# Hamamatsu_acond_2.net
KiCad netlist of a schematic drawn in Altium Designer
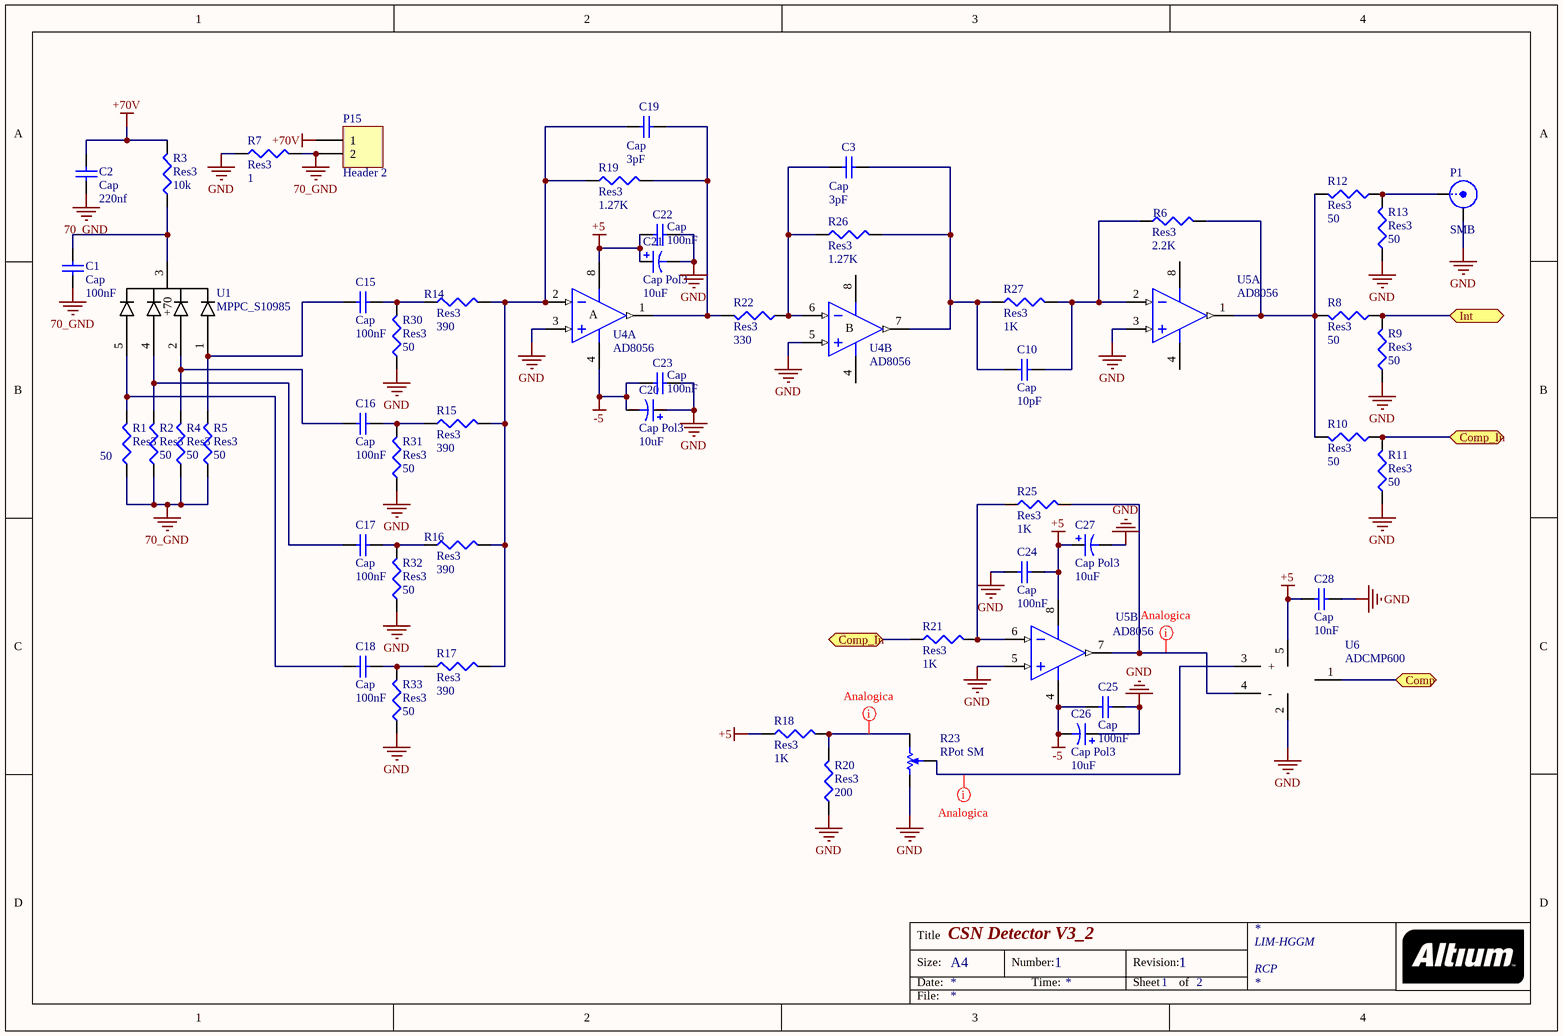
[diagram p0: Hamamatsu_acond_2.SchDoc]

(export (version "E")
  (design (tool "Eeschema 10.0.6"))
  (components
    (comp (ref "C1")
      (value "Cap")
      (footprint "C0805")
      (description "Capacitor")
      (fields (field (name "ALTIUM_VALUE") "100nF") (field (name "PUBLISHER") "Altium Limited"))
      (libsource (lib "Miscellaneous Devices") (part "Cap"))
    )
    (comp (ref "C2")
      (value "Cap")
      (footprint "C0805")
      (description "Capacitor")
      (fields (field (name "ALTIUM_VALUE") "220nf") (field (name "PUBLISHER") "Altium Limited"))
      (libsource (lib "Miscellaneous Devices") (part "Cap"))
    )
    (comp (ref "C3")
      (value "Cap")
      (footprint "C0805")
      (description "Capacitor")
      (fields (field (name "ALTIUM_VALUE") "3pF") (field (name "PUBLISHER") "Altium Limited"))
      (libsource (lib "Miscellaneous Devices") (part "Cap"))
    )
    (comp (ref "C10")
      (value "Cap")
      (footprint "C0805")
      (description "Capacitor")
      (fields (field (name "ALTIUM_VALUE") "10pF") (field (name "PUBLISHER") "Altium Limited"))
      (libsource (lib "Miscellaneous Devices") (part "Cap"))
    )
    (comp (ref "C15")
      (value "Cap")
      (footprint "C0805")
      (description "Capacitor")
      (fields (field (name "ALTIUM_VALUE") "100nF") (field (name "PUBLISHER") "Altium Limited"))
      (libsource (lib "Miscellaneous Devices") (part "Cap"))
    )
    (comp (ref "C16")
      (value "Cap")
      (footprint "C0805")
      (description "Capacitor")
      (fields (field (name "ALTIUM_VALUE") "100nF") (field (name "PUBLISHER") "Altium Limited"))
      (libsource (lib "Miscellaneous Devices") (part "Cap"))
    )
    (comp (ref "C17")
      (value "Cap")
      (footprint "C0805")
      (description "Capacitor")
      (fields (field (name "ALTIUM_VALUE") "100nF") (field (name "PUBLISHER") "Altium Limited"))
      (libsource (lib "Miscellaneous Devices") (part "Cap"))
    )
    (comp (ref "C18")
      (value "Cap")
      (footprint "C0805")
      (description "Capacitor")
      (fields (field (name "ALTIUM_VALUE") "100nF") (field (name "PUBLISHER") "Altium Limited"))
      (libsource (lib "Miscellaneous Devices") (part "Cap"))
    )
    (comp (ref "C19")
      (value "Cap")
      (footprint "C0805")
      (description "Capacitor")
      (fields (field (name "ALTIUM_VALUE") "3pF") (field (name "PUBLISHER") "Altium Limited"))
      (libsource (lib "Miscellaneous Devices") (part "Cap"))
    )
    (comp (ref "C20")
      (value "Cap Pol3")
      (footprint "6-0805_N")
      (description "Polarized Capacitor (Surface Mount)")
      (fields (field (name "ALTIUM_VALUE") "10uF") (field (name "PUBLISHER") "Altium Limited"))
      (libsource (lib "Miscellaneous Devices") (part "Cap Pol3"))
    )
    (comp (ref "C21")
      (value "Cap Pol3")
      (footprint "6-0805_N")
      (description "Polarized Capacitor (Surface Mount)")
      (fields (field (name "ALTIUM_VALUE") "10uF") (field (name "PUBLISHER") "Altium Limited"))
      (libsource (lib "Miscellaneous Devices") (part "Cap Pol3"))
    )
    (comp (ref "C22")
      (value "Cap")
      (footprint "6-0805_N")
      (description "Capacitor")
      (fields (field (name "ALTIUM_VALUE") "100nF") (field (name "PUBLISHER") "Altium Limited"))
      (libsource (lib "Miscellaneous Devices") (part "Cap"))
    )
    (comp (ref "C23")
      (value "Cap")
      (footprint "6-0805_N")
      (description "Capacitor")
      (fields (field (name "ALTIUM_VALUE") "100nF") (field (name "PUBLISHER") "Altium Limited"))
      (libsource (lib "Miscellaneous Devices") (part "Cap"))
    )
    (comp (ref "C24")
      (value "Cap")
      (footprint "6-0805_N")
      (description "Capacitor")
      (fields (field (name "ALTIUM_VALUE") "100nF") (field (name "PUBLISHER") "Altium Limited"))
      (libsource (lib "Miscellaneous Devices") (part "Cap"))
    )
    (comp (ref "C25")
      (value "Cap")
      (footprint "6-0805_N")
      (description "Capacitor")
      (fields (field (name "ALTIUM_VALUE") "100nF") (field (name "PUBLISHER") "Altium Limited"))
      (libsource (lib "Miscellaneous Devices") (part "Cap"))
    )
    (comp (ref "C26")
      (value "Cap Pol3")
      (footprint "6-0805_N")
      (description "Polarized Capacitor (Surface Mount)")
      (fields (field (name "ALTIUM_VALUE") "10uF") (field (name "PUBLISHER") "Altium Limited"))
      (libsource (lib "Miscellaneous Devices") (part "Cap Pol3"))
    )
    (comp (ref "C27")
      (value "Cap Pol3")
      (footprint "6-0805_N")
      (description "Polarized Capacitor (Surface Mount)")
      (fields (field (name "ALTIUM_VALUE") "10uF") (field (name "PUBLISHER") "Altium Limited"))
      (libsource (lib "Miscellaneous Devices") (part "Cap Pol3"))
    )
    (comp (ref "C28")
      (value "Cap")
      (footprint "6-0805_N")
      (description "Capacitor")
      (fields (field (name "ALTIUM_VALUE") "10nF") (field (name "PUBLISHER") "Altium Limited"))
      (libsource (lib "Miscellaneous Devices") (part "Cap"))
    )
    (comp (ref "P1")
      (value "SMB")
      (footprint "SMB_V-RJ45")
      (description "SMB Straight Connector")
      (fields (field (name "PUBLISHER") "Altium Limited"))
      (libsource (lib "Miscellaneous Connectors") (part "SMB"))
    )
    (comp (ref "P15")
      (value "Header 2")
      (footprint "HDR1X2")
      (description "Header, 2-Pin")
      (fields (field (name "PUBLISHER") "Altium Limited"))
      (libsource (lib "Miscellaneous Connectors") (part "Header 2"))
    )
    (comp (ref "R1")
      (value "Res3")
      (footprint "6-0805_N")
      (description "Resistor")
      (fields (field (name "ALTIUM_VALUE") "50") (field (name "PUBLISHER") "Altium Limited"))
      (libsource (lib "Miscellaneous Devices") (part "Res3"))
    )
    (comp (ref "R2")
      (value "Res3")
      (footprint "6-0805_N")
      (description "Resistor")
      (fields (field (name "ALTIUM_VALUE") "50") (field (name "PUBLISHER") "Altium Limited"))
      (libsource (lib "Miscellaneous Devices") (part "Res3"))
    )
    (comp (ref "R3")
      (value "Res3")
      (footprint "6-0805_N")
      (description "Resistor")
      (fields (field (name "ALTIUM_VALUE") "10k") (field (name "PUBLISHER") "Altium Limited"))
      (libsource (lib "Miscellaneous Devices") (part "Res3"))
    )
    (comp (ref "R4")
      (value "Res3")
      (footprint "6-0805_N")
      (description "Resistor")
      (fields (field (name "ALTIUM_VALUE") "50") (field (name "PUBLISHER") "Altium Limited"))
      (libsource (lib "Miscellaneous Devices") (part "Res3"))
    )
    (comp (ref "R5")
      (value "Res3")
      (footprint "6-0805_N")
      (description "Resistor")
      (fields (field (name "ALTIUM_VALUE") "50") (field (name "PUBLISHER") "Altium Limited"))
      (libsource (lib "Miscellaneous Devices") (part "Res3"))
    )
    (comp (ref "R6")
      (value "Res3")
      (footprint "6-0805_N")
      (description "Resistor")
      (fields (field (name "ALTIUM_VALUE") "2.2K") (field (name "PUBLISHER") "Altium Limited"))
      (libsource (lib "Miscellaneous Devices") (part "Res3"))
    )
    (comp (ref "R7")
      (value "Res3")
      (footprint "6-0805_N")
      (description "Resistor")
      (fields (field (name "ALTIUM_VALUE") "1") (field (name "PUBLISHER") "Altium Limited"))
      (libsource (lib "Miscellaneous Devices") (part "Res3"))
    )
    (comp (ref "R8")
      (value "Res3")
      (footprint "6-0805_N")
      (description "Resistor")
      (fields (field (name "ALTIUM_VALUE") "50") (field (name "PUBLISHER") "Altium Limited"))
      (libsource (lib "Miscellaneous Devices") (part "Res3"))
    )
    (comp (ref "R9")
      (value "Res3")
      (footprint "6-0805_N")
      (description "Resistor")
      (fields (field (name "ALTIUM_VALUE") "50") (field (name "PUBLISHER") "Altium Limited"))
      (libsource (lib "Miscellaneous Devices") (part "Res3"))
    )
    (comp (ref "R10")
      (value "Res3")
      (footprint "6-0805_N")
      (description "Resistor")
      (fields (field (name "ALTIUM_VALUE") "50") (field (name "PUBLISHER") "Altium Limited"))
      (libsource (lib "Miscellaneous Devices") (part "Res3"))
    )
    (comp (ref "R11")
      (value "Res3")
      (footprint "6-0805_N")
      (description "Resistor")
      (fields (field (name "ALTIUM_VALUE") "50") (field (name "PUBLISHER") "Altium Limited"))
      (libsource (lib "Miscellaneous Devices") (part "Res3"))
    )
    (comp (ref "R12")
      (value "Res3")
      (footprint "6-0805_N")
      (description "Resistor")
      (fields (field (name "ALTIUM_VALUE") "50") (field (name "PUBLISHER") "Altium Limited"))
      (libsource (lib "Miscellaneous Devices") (part "Res3"))
    )
    (comp (ref "R13")
      (value "Res3")
      (footprint "6-0805_N")
      (description "Resistor")
      (fields (field (name "ALTIUM_VALUE") "50") (field (name "PUBLISHER") "Altium Limited"))
      (libsource (lib "Miscellaneous Devices") (part "Res3"))
    )
    (comp (ref "R14")
      (value "Res3")
      (footprint "6-0805_N")
      (description "Resistor")
      (fields (field (name "ALTIUM_VALUE") "390") (field (name "PUBLISHER") "Altium Limited"))
      (libsource (lib "Miscellaneous Devices") (part "Res3"))
    )
    (comp (ref "R15")
      (value "Res3")
      (footprint "6-0805_N")
      (description "Resistor")
      (fields (field (name "ALTIUM_VALUE") "390") (field (name "PUBLISHER") "Altium Limited"))
      (libsource (lib "Miscellaneous Devices") (part "Res3"))
    )
    (comp (ref "R16")
      (value "Res3")
      (footprint "6-0805_N")
      (description "Resistor")
      (fields (field (name "ALTIUM_VALUE") "390") (field (name "PUBLISHER") "Altium Limited"))
      (libsource (lib "Miscellaneous Devices") (part "Res3"))
    )
    (comp (ref "R17")
      (value "Res3")
      (footprint "6-0805_N")
      (description "Resistor")
      (fields (field (name "ALTIUM_VALUE") "390") (field (name "PUBLISHER") "Altium Limited"))
      (libsource (lib "Miscellaneous Devices") (part "Res3"))
    )
    (comp (ref "R18")
      (value "Res3")
      (footprint "6-0805_N")
      (description "Resistor")
      (fields (field (name "ALTIUM_VALUE") "1K") (field (name "PUBLISHER") "Altium Limited"))
      (libsource (lib "Miscellaneous Devices") (part "Res3"))
    )
    (comp (ref "R19")
      (value "Res3")
      (footprint "6-0805_N")
      (description "Resistor")
      (fields (field (name "ALTIUM_VALUE") "1.27K") (field (name "PUBLISHER") "Altium Limited"))
      (libsource (lib "Miscellaneous Devices") (part "Res3"))
    )
    (comp (ref "R20")
      (value "Res3")
      (footprint "6-0805_N")
      (description "Resistor")
      (fields (field (name "ALTIUM_VALUE") "200") (field (name "PUBLISHER") "Altium Limited"))
      (libsource (lib "Miscellaneous Devices") (part "Res3"))
    )
    (comp (ref "R21")
      (value "Res3")
      (footprint "6-0805_N")
      (description "Resistor")
      (fields (field (name "ALTIUM_VALUE") "1K") (field (name "PUBLISHER") "Altium Limited"))
      (libsource (lib "Miscellaneous Devices") (part "Res3"))
    )
    (comp (ref "R22")
      (value "Res3")
      (footprint "6-0805_N")
      (description "Resistor")
      (fields (field (name "ALTIUM_VALUE") "330") (field (name "PUBLISHER") "Altium Limited"))
      (libsource (lib "Miscellaneous Devices") (part "Res3"))
    )
    (comp (ref "R23")
      (value "RPot SM")
      (footprint "POT4MM-2")
      (description "Square Trimming Potentiometer")
      (fields (field (name "PUBLISHER") "Altium Limited"))
      (libsource (lib "Miscellaneous Devices") (part "RPot SM"))
    )
    (comp (ref "R25")
      (value "Res3")
      (footprint "6-0805_N")
      (description "Resistor")
      (fields (field (name "ALTIUM_VALUE") "1K") (field (name "PUBLISHER") "Altium Limited"))
      (libsource (lib "Miscellaneous Devices") (part "Res3"))
    )
    (comp (ref "R26")
      (value "Res3")
      (footprint "6-0805_N")
      (description "Resistor")
      (fields (field (name "ALTIUM_VALUE") "1.27K") (field (name "PUBLISHER") "Altium Limited"))
      (libsource (lib "Miscellaneous Devices") (part "Res3"))
    )
    (comp (ref "R27")
      (value "Res3")
      (footprint "6-0805_N")
      (description "Resistor")
      (fields (field (name "ALTIUM_VALUE") "1K") (field (name "PUBLISHER") "Altium Limited"))
      (libsource (lib "Miscellaneous Devices") (part "Res3"))
    )
    (comp (ref "R30")
      (value "Res3")
      (footprint "6-0805_N")
      (description "Resistor")
      (fields (field (name "ALTIUM_VALUE") "50") (field (name "PUBLISHER") "Altium Limited"))
      (libsource (lib "Miscellaneous Devices") (part "Res3"))
    )
    (comp (ref "R31")
      (value "Res3")
      (footprint "6-0805_N")
      (description "Resistor")
      (fields (field (name "ALTIUM_VALUE") "50") (field (name "PUBLISHER") "Altium Limited"))
      (libsource (lib "Miscellaneous Devices") (part "Res3"))
    )
    (comp (ref "R32")
      (value "Res3")
      (footprint "6-0805_N")
      (description "Resistor")
      (fields (field (name "ALTIUM_VALUE") "50") (field (name "PUBLISHER") "Altium Limited"))
      (libsource (lib "Miscellaneous Devices") (part "Res3"))
    )
    (comp (ref "R33")
      (value "Res3")
      (footprint "6-0805_N")
      (description "Resistor")
      (fields (field (name "ALTIUM_VALUE") "50") (field (name "PUBLISHER") "Altium Limited"))
      (libsource (lib "Miscellaneous Devices") (part "Res3"))
    )
    (comp (ref "U1")
      (value "MPPC_S10985")
      (footprint "S10985_HAM")
      (libsource (lib "Int_Lib1") (part "MPPC_S10985"))
    )
    (comp (ref "U4")
      (value "AD8056")
      (footprint "SO-8_M")
      (description "Dual 600MHz, 50mW Current Feedback Amplifier")
      (fields (field (name "PUBLISHER") "Altium Limited"))
      (libsource (lib "AD Operational Amplifier") (part "AD8002AR"))
    )
    (comp (ref "U5")
      (value "AD8056")
      (footprint "S8_N")
      (description "Low Cost Dual Video Amplifier")
      (fields (field (name "PUBLISHER") "Altium Limited"))
      (libsource (lib "LT Video Amplifier") (part "LT1253CS8"))
    )
    (comp (ref "U6") (value "ADCMP600") (footprint "SOT23-5_N") (libsource (lib "Schlib1") (part "ADCMP600")))
  )
  (nets
    (net (code "1") (name "+5") (class "Default")
      (node (ref "C21") (pin "1") (pinfunction "1_1") (pintype "passive"))
      (node (ref "C22") (pin "2") (pinfunction "2_2") (pintype "passive"))
      (node (ref "C24") (pin "2") (pinfunction "2_2") (pintype "passive"))
      (node (ref "C27") (pin "1") (pinfunction "1_1") (pintype "passive"))
      (node (ref "C28") (pin "1") (pinfunction "1_1") (pintype "passive"))
      (node (ref "R18") (pin "1") (pinfunction "1_1") (pintype "passive"))
      (node (ref "U4") (pin "8") (pinfunction "V+_8") (pintype "power_in"))
      (node (ref "U5") (pin "8") (pinfunction "V+_8") (pintype "power_in"))
      (node (ref "U6") (pin "5") (pintype "power_in"))
    )
    (net (code "2") (name "+70V") (class "Default")
      (node (ref "C2") (pin "2") (pinfunction "2_2") (pintype "passive"))
      (node (ref "P15") (pin "1") (pinfunction "1_1") (pintype "passive"))
      (node (ref "R3") (pin "2") (pinfunction "2_2") (pintype "passive"))
    )
    (net (code "3") (name "-5") (class "Default")
      (node (ref "C20") (pin "2") (pinfunction "2_2") (pintype "passive"))
      (node (ref "C23") (pin "2") (pinfunction "2_2") (pintype "passive"))
      (node (ref "C25") (pin "1") (pinfunction "1_1") (pintype "passive"))
      (node (ref "C26") (pin "2") (pinfunction "2_2") (pintype "passive"))
      (node (ref "U4") (pin "4") (pinfunction "V-_4") (pintype "power_in"))
      (node (ref "U5") (pin "4") (pinfunction "V-_4") (pintype "power_in"))
    )
    (net (code "4") (name "/Comp") (class "Default") (node (ref "U6") (pin "1") (pintype "passive")))
    (net (code "5") (name "/Comp_In") (class "Default")
      (node (ref "R10") (pin "1") (pinfunction "1_1") (pintype "passive"))
      (node (ref "R11") (pin "2") (pinfunction "2_2") (pintype "passive"))
      (node (ref "R21") (pin "1") (pinfunction "1_1") (pintype "passive"))
    )
    (net (code "6") (name "/Int") (class "Default")
      (node (ref "R8") (pin "1") (pinfunction "1_1") (pintype "passive"))
      (node (ref "R9") (pin "2") (pinfunction "2_2") (pintype "passive"))
    )
    (net (code "7") (name "70_GND") (class "Default")
      (node (ref "C1") (pin "1") (pinfunction "1_1") (pintype "passive"))
      (node (ref "C2") (pin "1") (pinfunction "1_1") (pintype "passive"))
      (node (ref "P15") (pin "2") (pinfunction "2_2") (pintype "passive"))
      (node (ref "R1") (pin "1") (pinfunction "1_1") (pintype "passive"))
      (node (ref "R2") (pin "1") (pinfunction "1_1") (pintype "passive"))
      (node (ref "R4") (pin "1") (pinfunction "1_1") (pintype "passive"))
      (node (ref "R5") (pin "1") (pinfunction "1_1") (pintype "passive"))
      (node (ref "R7") (pin "2") (pinfunction "2_2") (pintype "passive"))
    )
    (net (code "8") (name "GND") (class "Default")
      (node (ref "C20") (pin "1") (pinfunction "1_1") (pintype "passive"))
      (node (ref "C21") (pin "2") (pinfunction "2_2") (pintype "passive"))
      (node (ref "C22") (pin "1") (pinfunction "1_1") (pintype "passive"))
      (node (ref "C23") (pin "1") (pinfunction "1_1") (pintype "passive"))
      (node (ref "C24") (pin "1") (pinfunction "1_1") (pintype "passive"))
      (node (ref "C25") (pin "2") (pinfunction "2_2") (pintype "passive"))
      (node (ref "C26") (pin "1") (pinfunction "1_1") (pintype "passive"))
      (node (ref "C27") (pin "2") (pinfunction "2_2") (pintype "passive"))
      (node (ref "C28") (pin "2") (pinfunction "2_2") (pintype "passive"))
      (node (ref "P1") (pin "2") (pinfunction "Y_2") (pintype "passive"))
      (node (ref "R11") (pin "1") (pinfunction "1_1") (pintype "passive"))
      (node (ref "R13") (pin "1") (pinfunction "1_1") (pintype "passive"))
      (node (ref "R20") (pin "1") (pinfunction "1_1") (pintype "passive"))
      (node (ref "R23") (pin "CCW") (pinfunction "-_CCW") (pintype "passive"))
      (node (ref "R30") (pin "1") (pinfunction "1_1") (pintype "passive"))
      (node (ref "R31") (pin "1") (pinfunction "1_1") (pintype "passive"))
      (node (ref "R32") (pin "1") (pinfunction "1_1") (pintype "passive"))
      (node (ref "R33") (pin "1") (pinfunction "1_1") (pintype "passive"))
      (node (ref "R7") (pin "1") (pinfunction "1_1") (pintype "passive"))
      (node (ref "R9") (pin "1") (pinfunction "1_1") (pintype "passive"))
      (node (ref "U4") (pin "3") (pinfunction "IN+_3") (pintype "input"))
      (node (ref "U4") (pin "5") (pinfunction "IN+_5") (pintype "input"))
      (node (ref "U5") (pin "3") (pinfunction "IN+_3") (pintype "input"))
      (node (ref "U5") (pin "5") (pinfunction "IN+_5") (pintype "input"))
      (node (ref "U6") (pin "2") (pintype "power_in"))
    )
    (net (code "9") (name "Net-(C15-Pad2)") (class "Default")
      (node (ref "C15") (pin "2") (pinfunction "2_2") (pintype "passive"))
      (node (ref "R14") (pin "1") (pinfunction "1_1") (pintype "passive"))
      (node (ref "R30") (pin "2") (pinfunction "2_2") (pintype "passive"))
    )
    (net (code "10") (name "Net-(C16-Pad2)") (class "Default")
      (node (ref "C16") (pin "2") (pinfunction "2_2") (pintype "passive"))
      (node (ref "R15") (pin "1") (pinfunction "1_1") (pintype "passive"))
      (node (ref "R31") (pin "2") (pinfunction "2_2") (pintype "passive"))
    )
    (net (code "11") (name "Net-(C17-Pad1)") (class "Default")
      (node (ref "C17") (pin "1") (pinfunction "1_1") (pintype "passive"))
      (node (ref "R2") (pin "2") (pinfunction "2_2") (pintype "passive"))
      (node (ref "U1") (pin "4") (pinfunction "4_4") (pintype "passive"))
    )
    (net (code "12") (name "Net-(C17-Pad2)") (class "Default")
      (node (ref "C17") (pin "2") (pinfunction "2_2") (pintype "passive"))
      (node (ref "R16") (pin "1") (pinfunction "1_1") (pintype "passive"))
      (node (ref "R32") (pin "2") (pinfunction "2_2") (pintype "passive"))
    )
    (net (code "13") (name "Net-(C18-Pad1)") (class "Default")
      (node (ref "C18") (pin "1") (pinfunction "1_1") (pintype "passive"))
      (node (ref "R1") (pin "2") (pinfunction "2_2") (pintype "passive"))
      (node (ref "U1") (pin "5") (pinfunction "5_5") (pintype "passive"))
    )
    (net (code "14") (name "Net-(C18-Pad2)") (class "Default")
      (node (ref "C18") (pin "2") (pinfunction "2_2") (pintype "passive"))
      (node (ref "R17") (pin "1") (pinfunction "1_1") (pintype "passive"))
      (node (ref "R33") (pin "2") (pinfunction "2_2") (pintype "passive"))
    )
    (net (code "15") (name "Net-(P1-X)") (class "Default")
      (node (ref "P1") (pin "1") (pinfunction "X_1") (pintype "passive"))
      (node (ref "R12") (pin "1") (pinfunction "1_1") (pintype "passive"))
      (node (ref "R13") (pin "2") (pinfunction "2_2") (pintype "passive"))
    )
    (net (code "16") (name "Net-(R23-+)") (class "Default")
      (node (ref "R18") (pin "2") (pinfunction "2_2") (pintype "passive"))
      (node (ref "R20") (pin "2") (pinfunction "2_2") (pintype "passive"))
      (node (ref "R23") (pin "CW") (pinfunction "+_CW") (pintype "passive"))
    )
    (net (code "17") (name "Net-(U1-+70)") (class "Default")
      (node (ref "C1") (pin "2") (pinfunction "2_2") (pintype "passive"))
      (node (ref "R3") (pin "1") (pinfunction "1_1") (pintype "passive"))
      (node (ref "U1") (pin "3") (pinfunction "+70_3") (pintype "passive"))
    )
    (net (code "18") (name "Net-(U1-Pin1)") (class "Default")
      (node (ref "C15") (pin "1") (pinfunction "1_1") (pintype "passive"))
      (node (ref "R5") (pin "2") (pinfunction "2_2") (pintype "passive"))
      (node (ref "U1") (pin "1") (pinfunction "Pin1_1") (pintype "passive"))
    )
    (net (code "19") (name "Net-(U1-Pin2)") (class "Default")
      (node (ref "C16") (pin "1") (pinfunction "1_1") (pintype "passive"))
      (node (ref "R4") (pin "2") (pinfunction "2_2") (pintype "passive"))
      (node (ref "U1") (pin "2") (pinfunction "Pin2_2") (pintype "passive"))
    )
    (net (code "20") (name "Net-(U4A-IN-)") (class "Default")
      (node (ref "C19") (pin "1") (pinfunction "1_1") (pintype "passive"))
      (node (ref "R14") (pin "2") (pinfunction "2_2") (pintype "passive"))
      (node (ref "R15") (pin "2") (pinfunction "2_2") (pintype "passive"))
      (node (ref "R16") (pin "2") (pinfunction "2_2") (pintype "passive"))
      (node (ref "R17") (pin "2") (pinfunction "2_2") (pintype "passive"))
      (node (ref "R19") (pin "1") (pinfunction "1_1") (pintype "passive"))
      (node (ref "U4") (pin "2") (pinfunction "IN-_2") (pintype "input"))
    )
    (net (code "21") (name "Net-(U4A-OUT)") (class "Default")
      (node (ref "C19") (pin "2") (pinfunction "2_2") (pintype "passive"))
      (node (ref "R19") (pin "2") (pinfunction "2_2") (pintype "passive"))
      (node (ref "R22") (pin "2") (pinfunction "2_2") (pintype "passive"))
      (node (ref "U4") (pin "1") (pinfunction "OUT_1") (pintype "output"))
    )
    (net (code "22") (name "Net-(U4B-IN-)") (class "Default")
      (node (ref "C3") (pin "1") (pinfunction "1_1") (pintype "passive"))
      (node (ref "R22") (pin "1") (pinfunction "1_1") (pintype "passive"))
      (node (ref "R26") (pin "1") (pinfunction "1_1") (pintype "passive"))
      (node (ref "U4") (pin "6") (pinfunction "IN-_6") (pintype "input"))
    )
    (net (code "23") (name "Net-(U4B-OUT)") (class "Default")
      (node (ref "C10") (pin "1") (pinfunction "1_1") (pintype "passive"))
      (node (ref "C3") (pin "2") (pinfunction "2_2") (pintype "passive"))
      (node (ref "R26") (pin "2") (pinfunction "2_2") (pintype "passive"))
      (node (ref "R27") (pin "1") (pinfunction "1_1") (pintype "passive"))
      (node (ref "U4") (pin "7") (pinfunction "OUT_7") (pintype "output"))
    )
    (net (code "24") (name "Net-(U5A-IN-)") (class "Default")
      (node (ref "C10") (pin "2") (pinfunction "2_2") (pintype "passive"))
      (node (ref "R27") (pin "2") (pinfunction "2_2") (pintype "passive"))
      (node (ref "R6") (pin "1") (pinfunction "1_1") (pintype "passive"))
      (node (ref "U5") (pin "2") (pinfunction "IN-_2") (pintype "input"))
    )
    (net (code "25") (name "Net-(U5A-OUT)") (class "Default")
      (node (ref "R10") (pin "2") (pinfunction "2_2") (pintype "passive"))
      (node (ref "R12") (pin "2") (pinfunction "2_2") (pintype "passive"))
      (node (ref "R6") (pin "2") (pinfunction "2_2") (pintype "passive"))
      (node (ref "R8") (pin "2") (pinfunction "2_2") (pintype "passive"))
      (node (ref "U5") (pin "1") (pinfunction "OUT_1") (pintype "output"))
    )
    (net (code "26") (name "Net-(U5B-IN-)") (class "Default")
      (node (ref "R21") (pin "2") (pinfunction "2_2") (pintype "passive"))
      (node (ref "R25") (pin "1") (pinfunction "1_1") (pintype "passive"))
      (node (ref "U5") (pin "6") (pinfunction "IN-_6") (pintype "input"))
    )
    (net (code "27") (name "Net-(U5B-OUT)") (class "Default")
      (node (ref "R25") (pin "2") (pinfunction "2_2") (pintype "passive"))
      (node (ref "U5") (pin "7") (pinfunction "OUT_7") (pintype "output"))
      (node (ref "U6") (pin "4") (pinfunction "-_4") (pintype "passive"))
    )
    (net (code "28") (name "Net-(U6-+)") (class "Default")
      (node (ref "R23") (pin "W") (pinfunction "W_W") (pintype "passive"))
      (node (ref "U6") (pin "3") (pinfunction "+_3") (pintype "passive"))
    )
    (net (code "29") (name "unconnected-(U4B-V+-Pad8)") (class "Default")
      (node (ref "U4") (pin "8") (pinfunction "V+_8") (pintype "power_in"))
    )
    (net (code "30") (name "unconnected-(U4B-V--Pad4)") (class "Default")
      (node (ref "U4") (pin "4") (pinfunction "V-_4") (pintype "power_in"))
    )
    (net (code "31") (name "unconnected-(U5A-V+-Pad8)") (class "Default")
      (node (ref "U5") (pin "8") (pinfunction "V+_8") (pintype "power_in"))
    )
    (net (code "32") (name "unconnected-(U5A-V--Pad4)") (class "Default")
      (node (ref "U5") (pin "4") (pinfunction "V-_4") (pintype "power_in"))
    )
  )
)
